# esp32_LoRa_radar_pelampung.net
KiCad netlist of a schematic drawn in EAGLE
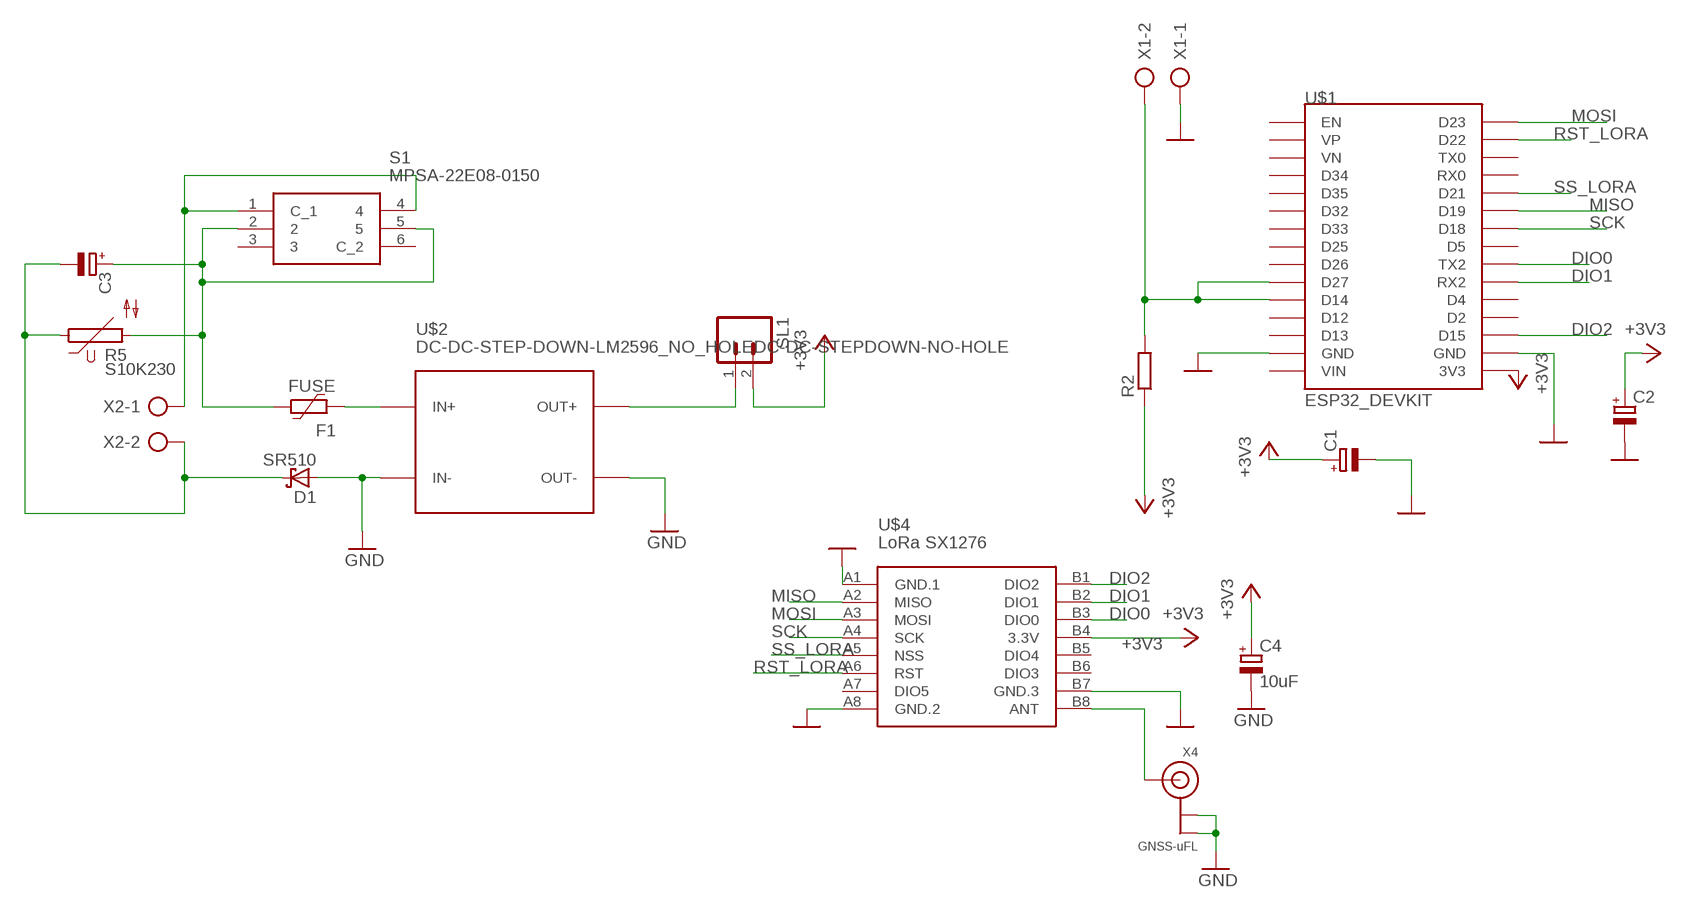
[diagram p0: schematic, sheet 1]

(export (version "E")
  (design (tool "Eeschema 10.0.6"))
  (components
    (comp (ref "C1")
      (value "CPOL-EUE5-8.5")
      (footprint "eagle-import:E5-8,5")
      (libsource (lib "eagle-import") (part "CPOL-EUE5-8.5"))
    )
    (comp (ref "C2")
      (value "CPOL-EUE5-8.5")
      (footprint "eagle-import:E5-8,5")
      (libsource (lib "eagle-import") (part "CPOL-EUE5-8.5"))
    )
    (comp (ref "C3")
      (value "CPOL-EUE5-13")
      (footprint "eagle-import:E5-13")
      (libsource (lib "eagle-import") (part "CPOL-EUE5-13"))
    )
    (comp (ref "C4")
      (value "10uF")
      (footprint "eagle-import:E2,5-6")
      (libsource (lib "eagle-import") (part "CPOL-EUE2.5-6"))
    )
    (comp (ref "D1")
      (value "SR510")
      (footprint "eagle-import:SMB")
      (libsource (lib "eagle-import") (part "SCHOTTKY-DIODESMD"))
    )
    (comp (ref "F1")
      (value "FUSE")
      (footprint "eagle-import:1812L")
      (fields (field (name "MF") "Littelfuse") (field (name "MPN") "1812L010"))
      (libsource (lib "eagle-import") (part "?1812L010"))
    )
    (comp (ref "R2")
      (value "R-EU_0309/12")
      (footprint "eagle-import:0309_12")
      (libsource (lib "eagle-import") (part "R-EU_0309/12"))
    )
    (comp (ref "R5")
      (value "S10K230")
      (footprint "eagle-import:S10K230")
      (libsource (lib "eagle-import") (part "S10K230"))
    )
    (comp (ref "S1")
      (value "MPSA-22E08-0150")
      (footprint "eagle-import:MPSA22E080150")
      (fields (field (name "RS_PART_NUMBER") "9138895"))
      (libsource (lib "eagle-import") (part "MPSA-22E08-0150"))
    )
    (comp (ref "SL1")
      (value "M02")
      (footprint "eagle-import:02P")
      (libsource (lib "eagle-import") (part "M02"))
    )
    (comp (ref "U$1")
      (value "ESP32_DEVKIT")
      (footprint "eagle-import:ESP32_DEVKIT")
      (libsource (lib "eagle-import") (part "ESP32_DEVKIT"))
    )
    (comp (ref "U$2")
      (value "DC-DC-STEP-DOWN-LM2596_NO_HOLEDC-DC-STEPDOWN-NO-HOLE")
      (footprint "eagle-import:DC-DC-STEP-DOWN-LM2596_NO_HOLE")
      (libsource (lib "eagle-import") (part "DC-DC-STEP-DOWN-LM2596_NO_HOLEDC-DC-STEPDOWN-NO-HOLE"))
    )
    (comp (ref "U$4")
      (value "LoRa SX1276")
      (footprint "eagle-import:WIRELESS-LORA-RFM95W#SMD")
      (libsource (lib "eagle-import") (part "WIRELESS-LORA-RFM95W#SMD"))
    )
    (comp (ref "X1")
      (value "AK300/2")
      (footprint "eagle-import:AK300_2")
      (libsource (lib "eagle-import") (part "AK300/2"))
    )
    (comp (ref "X2")
      (value "AK300/2")
      (footprint "eagle-import:AK300_2")
      (libsource (lib "eagle-import") (part "AK300/2"))
    )
    (comp (ref "X4")
      (value "GNSS-uFL")
      (footprint "eagle-import:U.FL")
      (libsource (lib "eagle-import") (part "ANTENNA_U.FL"))
    )
  )
  (nets
    (net (code "1") (name "+3V3") (class "Default")
      (node (ref "C1") (pin "+") (pinfunction "+_+") (pintype "passive"))
      (node (ref "C2") (pin "+") (pinfunction "+_+") (pintype "passive"))
      (node (ref "C4") (pin "+") (pinfunction "+_+") (pintype "passive"))
      (node (ref "R2") (pin "1") (pinfunction "1_1") (pintype "passive"))
      (node (ref "SL1") (pin "2") (pinfunction "2_2") (pintype "passive"))
      (node (ref "U$1") (pin "3V3") (pinfunction "3V3_3V3") (pintype "bidirectional"))
      (node (ref "U$4") (pin "B4") (pinfunction "3.3V_B4") (pintype "power_in"))
    )
    (net (code "2") (name "/DIO0") (class "Default")
      (node (ref "U$1") (pin "TX2") (pinfunction "TX2_TX2") (pintype "bidirectional"))
      (node (ref "U$4") (pin "B3") (pinfunction "DIO0_B3") (pintype "bidirectional"))
    )
    (net (code "3") (name "/DIO1") (class "Default")
      (node (ref "U$1") (pin "RX2") (pinfunction "RX2_RX2") (pintype "bidirectional"))
      (node (ref "U$4") (pin "B2") (pinfunction "DIO1_B2") (pintype "bidirectional"))
    )
    (net (code "4") (name "/DIO2") (class "Default")
      (node (ref "U$1") (pin "D15") (pinfunction "D15_D15") (pintype "bidirectional"))
      (node (ref "U$4") (pin "B1") (pinfunction "DIO2_B1") (pintype "bidirectional"))
    )
    (net (code "5") (name "/MISO") (class "Default")
      (node (ref "U$1") (pin "D19") (pinfunction "D19_D19") (pintype "bidirectional"))
      (node (ref "U$4") (pin "A2") (pinfunction "MISO_A2") (pintype "bidirectional"))
    )
    (net (code "6") (name "/MOSI") (class "Default")
      (node (ref "U$1") (pin "D23") (pinfunction "D23_D23") (pintype "bidirectional"))
      (node (ref "U$4") (pin "A3") (pinfunction "MOSI_A3") (pintype "bidirectional"))
    )
    (net (code "7") (name "/RST_LORA") (class "Default")
      (node (ref "U$1") (pin "D22") (pinfunction "D22_D22") (pintype "bidirectional"))
      (node (ref "U$4") (pin "A6") (pinfunction "RST_A6") (pintype "bidirectional"))
    )
    (net (code "8") (name "/SCK") (class "Default")
      (node (ref "U$1") (pin "D18") (pinfunction "D18_D18") (pintype "bidirectional"))
      (node (ref "U$4") (pin "A4") (pinfunction "SCK_A4") (pintype "bidirectional"))
    )
    (net (code "9") (name "/SS_LORA") (class "Default")
      (node (ref "U$1") (pin "D21") (pinfunction "D21_D21") (pintype "bidirectional"))
      (node (ref "U$4") (pin "A5") (pinfunction "NSS_A5") (pintype "bidirectional"))
    )
    (net (code "10") (name "GND") (class "Default")
      (node (ref "C1") (pin "-") (pinfunction "-_-") (pintype "passive"))
      (node (ref "C2") (pin "-") (pinfunction "-_-") (pintype "passive"))
      (node (ref "C4") (pin "-") (pinfunction "-_-") (pintype "passive"))
      (node (ref "D1") (pin "A") (pinfunction "A_A") (pintype "passive"))
      (node (ref "U$1") (pin "GND@1") (pinfunction "GND_GND@1") (pintype "bidirectional"))
      (node (ref "U$1") (pin "GND@2") (pinfunction "GND_GND@2") (pintype "bidirectional"))
      (node (ref "U$2") (pin "IN-") (pinfunction "IN-_IN-") (pintype "bidirectional"))
      (node (ref "U$2") (pin "OUT-") (pinfunction "OUT-_OUT-") (pintype "bidirectional"))
      (node (ref "U$4") (pin "A1") (pinfunction "GND.1_A1") (pintype "power_in"))
      (node (ref "U$4") (pin "A8") (pinfunction "GND.2_A8") (pintype "power_in"))
      (node (ref "U$4") (pin "B7") (pinfunction "GND.3_B7") (pintype "power_in"))
      (node (ref "X1") (pin "1") (pinfunction "KL_1") (pintype "passive"))
      (node (ref "X4") (pin "1") (pinfunction "GND_1") (pintype "passive"))
      (node (ref "X4") (pin "2") (pinfunction "GND_2") (pintype "passive"))
    )
    (net (code "11") (name "Net-(C3-Pad+)") (class "Default")
      (node (ref "C3") (pin "+") (pinfunction "+_+") (pintype "passive"))
      (node (ref "F1") (pin "1") (pinfunction "1_1") (pintype "passive"))
      (node (ref "R5") (pin "2") (pinfunction "2_2") (pintype "passive"))
      (node (ref "S1") (pin "2") (pinfunction "2_2") (pintype "bidirectional"))
      (node (ref "S1") (pin "5") (pinfunction "5_5") (pintype "bidirectional"))
    )
    (net (code "12") (name "Net-(F1-Pad2)") (class "Default")
      (node (ref "F1") (pin "2") (pinfunction "2_2") (pintype "passive"))
      (node (ref "U$2") (pin "IN+") (pinfunction "IN+_IN+") (pintype "bidirectional"))
    )
    (net (code "13") (name "Net-(S1-C_1)") (class "Default")
      (node (ref "S1") (pin "1") (pinfunction "C_1_1") (pintype "bidirectional"))
      (node (ref "S1") (pin "4") (pinfunction "4_4") (pintype "bidirectional"))
      (node (ref "X2") (pin "1") (pinfunction "KL_1") (pintype "passive"))
    )
    (net (code "14") (name "Net-(SL1-Pad1)") (class "Default")
      (node (ref "SL1") (pin "1") (pinfunction "1_1") (pintype "passive"))
      (node (ref "U$2") (pin "OUT+") (pinfunction "OUT+_OUT+") (pintype "bidirectional"))
    )
    (net (code "15") (name "Net-(U$4-ANT)") (class "Default")
      (node (ref "U$4") (pin "B8") (pinfunction "ANT_B8") (pintype "passive"))
      (node (ref "X4") (pin "3") (pinfunction "SIGNAL_3") (pintype "passive"))
    )
    (net (code "16") (name "Net-(X1B-KL)") (class "Default")
      (node (ref "R2") (pin "2") (pinfunction "2_2") (pintype "passive"))
      (node (ref "U$1") (pin "D14") (pinfunction "D14_D14") (pintype "bidirectional"))
      (node (ref "U$1") (pin "D27") (pinfunction "D27_D27") (pintype "bidirectional"))
      (node (ref "X1") (pin "2") (pinfunction "KL_2") (pintype "passive"))
    )
    (net (code "17") (name "Net-(X2B-KL)") (class "Default")
      (node (ref "C3") (pin "-") (pinfunction "-_-") (pintype "passive"))
      (node (ref "D1") (pin "C") (pinfunction "C_C") (pintype "passive"))
      (node (ref "R5") (pin "1") (pinfunction "1_1") (pintype "passive"))
      (node (ref "X2") (pin "2") (pinfunction "KL_2") (pintype "passive"))
    )
    (net (code "18") (name "unconnected-(S1-C_2-Pad6)") (class "Default")
      (node (ref "S1") (pin "6") (pinfunction "C_2_6") (pintype "bidirectional"))
    )
    (net (code "19") (name "unconnected-(S1-Pad3)") (class "Default")
      (node (ref "S1") (pin "3") (pinfunction "3_3") (pintype "bidirectional"))
    )
    (net (code "20") (name "unconnected-(U$1-PadD2)") (class "Default")
      (node (ref "U$1") (pin "D2") (pinfunction "D2_D2") (pintype "bidirectional"))
    )
    (net (code "21") (name "unconnected-(U$1-PadD4)") (class "Default")
      (node (ref "U$1") (pin "D4") (pinfunction "D4_D4") (pintype "bidirectional"))
    )
    (net (code "22") (name "unconnected-(U$1-PadD5)") (class "Default")
      (node (ref "U$1") (pin "D5") (pinfunction "D5_D5") (pintype "bidirectional"))
    )
    (net (code "23") (name "unconnected-(U$1-PadD12)") (class "Default")
      (node (ref "U$1") (pin "D12") (pinfunction "D12_D12") (pintype "bidirectional"))
    )
    (net (code "24") (name "unconnected-(U$1-PadD13)") (class "Default")
      (node (ref "U$1") (pin "D13") (pinfunction "D13_D13") (pintype "bidirectional"))
    )
    (net (code "25") (name "unconnected-(U$1-PadD25)") (class "Default")
      (node (ref "U$1") (pin "D25") (pinfunction "D25_D25") (pintype "bidirectional"))
    )
    (net (code "26") (name "unconnected-(U$1-PadD26)") (class "Default")
      (node (ref "U$1") (pin "D26") (pinfunction "D26_D26") (pintype "bidirectional"))
    )
    (net (code "27") (name "unconnected-(U$1-PadD32)") (class "Default")
      (node (ref "U$1") (pin "D32") (pinfunction "D32_D32") (pintype "bidirectional"))
    )
    (net (code "28") (name "unconnected-(U$1-PadD33)") (class "Default")
      (node (ref "U$1") (pin "D33") (pinfunction "D33_D33") (pintype "bidirectional"))
    )
    (net (code "29") (name "unconnected-(U$1-PadD34)") (class "Default")
      (node (ref "U$1") (pin "D34") (pinfunction "D34_D34") (pintype "bidirectional"))
    )
    (net (code "30") (name "unconnected-(U$1-PadD35)") (class "Default")
      (node (ref "U$1") (pin "D35") (pinfunction "D35_D35") (pintype "bidirectional"))
    )
    (net (code "31") (name "unconnected-(U$1-PadEN)") (class "Default")
      (node (ref "U$1") (pin "EN") (pinfunction "EN_EN") (pintype "bidirectional"))
    )
    (net (code "32") (name "unconnected-(U$1-PadRX0)") (class "Default")
      (node (ref "U$1") (pin "RX0") (pinfunction "RX0_RX0") (pintype "bidirectional"))
    )
    (net (code "33") (name "unconnected-(U$1-PadTX0)") (class "Default")
      (node (ref "U$1") (pin "TX0") (pinfunction "TX0_TX0") (pintype "bidirectional"))
    )
    (net (code "34") (name "unconnected-(U$1-PadVIN)") (class "Default")
      (node (ref "U$1") (pin "VIN") (pinfunction "VIN_VIN") (pintype "bidirectional"))
    )
    (net (code "35") (name "unconnected-(U$1-PadVN)") (class "Default")
      (node (ref "U$1") (pin "VN") (pinfunction "VN_VN") (pintype "bidirectional"))
    )
    (net (code "36") (name "unconnected-(U$1-PadVP)") (class "Default")
      (node (ref "U$1") (pin "VP") (pinfunction "VP_VP") (pintype "bidirectional"))
    )
    (net (code "37") (name "unconnected-(U$4-DIO3-PadB6)") (class "Default")
      (node (ref "U$4") (pin "B6") (pinfunction "DIO3_B6") (pintype "bidirectional"))
    )
    (net (code "38") (name "unconnected-(U$4-DIO4-PadB5)") (class "Default")
      (node (ref "U$4") (pin "B5") (pinfunction "DIO4_B5") (pintype "bidirectional"))
    )
    (net (code "39") (name "unconnected-(U$4-DIO5-PadA7)") (class "Default")
      (node (ref "U$4") (pin "A7") (pinfunction "DIO5_A7") (pintype "bidirectional"))
    )
  )
)
